# CPU.net
KiCad netlist of a schematic drawn in Altium Designer
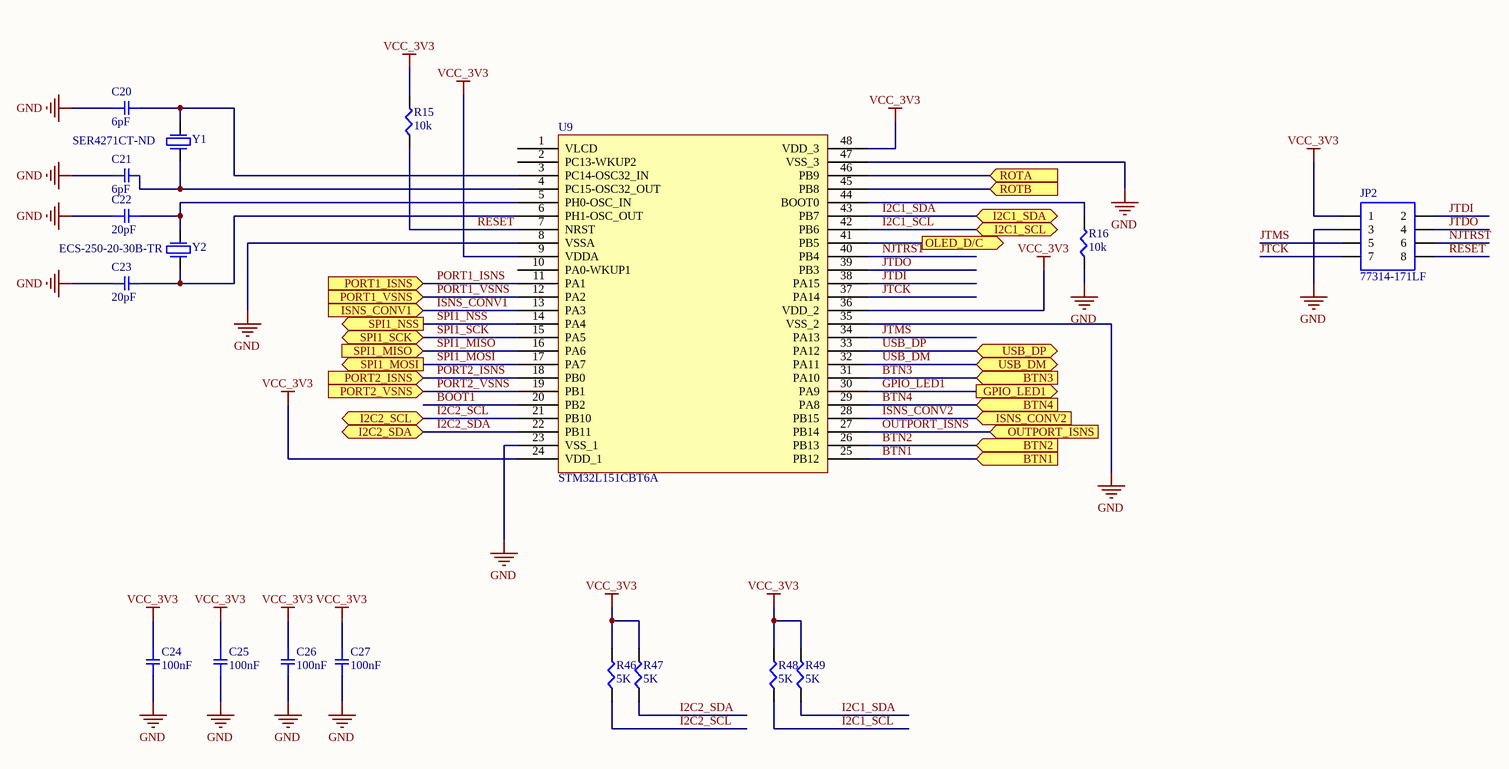
[diagram p0: CPU.SchDoc]

(export (version "E")
  (design (tool "Eeschema 10.0.6"))
  (components
    (comp (ref "C20")
      (value "6pF")
      (footprint "SMD-0805C")
      (description "CAP CER 0.1UF 50V X7R 0805")
      (fields
        (field (name "DIGI-KEY PART NUMBER") "490-6064-1-ND")
        (field (name "PART NUMBER") "GCM21BR71H104KA37L")
      )
      (libsource (lib "capacitor_murata_0805") (part "GCM21BR71H104KA37L"))
    )
    (comp (ref "C21")
      (value "6pF")
      (footprint "SMD-0805C")
      (description "CAP CER 0.1UF 50V X7R 0805")
      (fields
        (field (name "DIGI-KEY PART NUMBER") "490-6064-1-ND")
        (field (name "PART NUMBER") "GCM21BR71H104KA37L")
      )
      (libsource (lib "capacitor_murata_0805") (part "GCM21BR71H104KA37L"))
    )
    (comp (ref "C22")
      (value "20pF")
      (footprint "SMD-0805C")
      (description "CAP CER 0.1UF 50V X7R 0805")
      (fields
        (field (name "DIGI-KEY PART NUMBER") "490-6064-1-ND")
        (field (name "PART NUMBER") "GCM21BR71H104KA37L")
      )
      (libsource (lib "capacitor_murata_0805") (part "GCM21BR71H104KA37L"))
    )
    (comp (ref "C23")
      (value "20pF")
      (footprint "SMD-0805C")
      (description "CAP CER 0.1UF 50V X7R 0805")
      (fields
        (field (name "DIGI-KEY PART NUMBER") "490-6064-1-ND")
        (field (name "PART NUMBER") "GCM21BR71H104KA37L")
      )
      (libsource (lib "capacitor_murata_0805") (part "GCM21BR71H104KA37L"))
    )
    (comp (ref "C24")
      (value "100nF")
      (footprint "SMD-0805C")
      (description "CAP CER 0.1UF 50V X7R 0805")
      (fields
        (field (name "DIGI-KEY PART NUMBER") "490-6064-1-ND")
        (field (name "PART NUMBER") "GCM21BR71H104KA37L")
      )
      (libsource (lib "capacitor_murata_0805") (part "GCM21BR71H104KA37L"))
    )
    (comp (ref "C25")
      (value "100nF")
      (footprint "SMD-0805C")
      (description "CAP CER 0.1UF 50V X7R 0805")
      (fields
        (field (name "DIGI-KEY PART NUMBER") "490-6064-1-ND")
        (field (name "PART NUMBER") "GCM21BR71H104KA37L")
      )
      (libsource (lib "capacitor_murata_0805") (part "GCM21BR71H104KA37L"))
    )
    (comp (ref "C26")
      (value "100nF")
      (footprint "SMD-0805C")
      (description "CAP CER 0.1UF 50V X7R 0805")
      (fields
        (field (name "DIGI-KEY PART NUMBER") "490-6064-1-ND")
        (field (name "PART NUMBER") "GCM21BR71H104KA37L")
      )
      (libsource (lib "capacitor_murata_0805") (part "GCM21BR71H104KA37L"))
    )
    (comp (ref "C27")
      (value "100nF")
      (footprint "SMD-0805C")
      (description "CAP CER 0.1UF 50V X7R 0805")
      (fields
        (field (name "DIGI-KEY PART NUMBER") "490-6064-1-ND")
        (field (name "PART NUMBER") "GCM21BR71H104KA37L")
      )
      (libsource (lib "capacitor_murata_0805") (part "GCM21BR71H104KA37L"))
    )
    (comp (ref "JP2")
      (value "77314-171LF")
      (footprint "2x4 Pin Header")
      (description "CONN HEADER VERT 8POS 2.54MM")
      (libsource (lib "Personal_Library") (part "CONN HEADER VERT 2x4"))
    )
    (comp (ref "R15")
      (value "10k")
      (footprint "SMD-0603-RES")
      (description "RES SMD 1.6 OHM 1% 1/4W 0603")
      (fields (field (name "PART NUMBER") "ERJ-3BQF1R6V") (field (name "DIGI-KEY PART NUMBER") "P17375CT-ND"))
      (libsource (lib "Panasonic_ERJ_0603") (part "ERJ-3BQF1R6V"))
    )
    (comp (ref "R16")
      (value "10k")
      (footprint "SMD-0603-RES")
      (description "RES SMD 1.6 OHM 1% 1/4W 0603")
      (fields (field (name "PART NUMBER") "ERJ-3BQF1R6V") (field (name "DIGI-KEY PART NUMBER") "P17375CT-ND"))
      (libsource (lib "Panasonic_ERJ_0603") (part "ERJ-3BQF1R6V"))
    )
    (comp (ref "R46")
      (value "5K")
      (footprint "SMD-0603-RES")
      (description "RES SMD 1.5 OHM 1% 1/4W 0603")
      (fields (field (name "PART NUMBER") "ERJ-3BQF1R5V") (field (name "DIGI-KEY PART NUMBER") "P15988CT-ND"))
      (libsource (lib "Panasonic_ERJ_0603") (part "ERJ-3BQF1R5V"))
    )
    (comp (ref "R47")
      (value "5K")
      (footprint "SMD-0603-RES")
      (description "RES SMD 1.5 OHM 1% 1/4W 0603")
      (fields (field (name "PART NUMBER") "ERJ-3BQF1R5V") (field (name "DIGI-KEY PART NUMBER") "P15988CT-ND"))
      (libsource (lib "Panasonic_ERJ_0603") (part "ERJ-3BQF1R5V"))
    )
    (comp (ref "R48")
      (value "5K")
      (footprint "SMD-0603-RES")
      (description "RES SMD 1.5 OHM 1% 1/4W 0603")
      (fields (field (name "PART NUMBER") "ERJ-3BQF1R5V") (field (name "DIGI-KEY PART NUMBER") "P15988CT-ND"))
      (libsource (lib "Panasonic_ERJ_0603") (part "ERJ-3BQF1R5V"))
    )
    (comp (ref "R49")
      (value "5K")
      (footprint "SMD-0603-RES")
      (description "RES SMD 1.5 OHM 1% 1/4W 0603")
      (fields (field (name "PART NUMBER") "ERJ-3BQF1R5V") (field (name "DIGI-KEY PART NUMBER") "P15988CT-ND"))
      (libsource (lib "Panasonic_ERJ_0603") (part "ERJ-3BQF1R5V"))
    )
    (comp (ref "U9")
      (value "STM32L151CBT6A")
      (footprint "LQFP_151CBT6A_STM")
      (description "No Description Available")
      (fields (field (name "COPYRIGHT") "Copyright (C) 2018 Accelerated Designs. All rights reserved"))
      (libsource (lib "UniversalConverter_Parts") (part "IC STM32L151CBT6A_1"))
    )
    (comp (ref "Y1")
      (value "SER4271CT-ND")
      (footprint "ABS07-120")
      (description "32.768kHz ±20ppm Crystal 6pF 55 kOhms 2-SMD, No Lead")
      (libsource (lib "Personal_Library") (part "CRYSTAL 32.7680KHZ"))
    )
    (comp (ref "Y2")
      (value "ECS-250-20-30B-TR")
      (footprint "4-SMD XTAL")
      (description "CRYSTAL 20MHZ 18PF SMD")
      (libsource (lib "Personal_Library") (part "CRYSTAL 20MHZ"))
    )
  )
  (nets
    (net (code "1") (name "/BOOT1") (class "Default")
      (node (ref "U9") (pin "20") (pinfunction "PB2_20") (pintype "passive"))
    )
    (net (code "2") (name "/BTN1") (class "Default")
      (node (ref "U9") (pin "25") (pinfunction "PB12_25") (pintype "passive"))
    )
    (net (code "3") (name "/BTN2") (class "Default")
      (node (ref "U9") (pin "26") (pinfunction "PB13_26") (pintype "passive"))
    )
    (net (code "4") (name "/BTN3") (class "Default")
      (node (ref "U9") (pin "31") (pinfunction "PA10_31") (pintype "passive"))
    )
    (net (code "5") (name "/BTN4") (class "Default")
      (node (ref "U9") (pin "29") (pinfunction "PA8_29") (pintype "passive"))
    )
    (net (code "6") (name "/GPIO_LED1") (class "Default")
      (node (ref "U9") (pin "30") (pinfunction "PA9_30") (pintype "passive"))
    )
    (net (code "7") (name "/I2C1_SCL") (class "Default")
      (node (ref "R48") (pin "1") (pinfunction "1_1") (pintype "passive"))
      (node (ref "U9") (pin "42") (pinfunction "PB6_42") (pintype "passive"))
    )
    (net (code "8") (name "/I2C1_SDA") (class "Default")
      (node (ref "R49") (pin "1") (pinfunction "1_1") (pintype "passive"))
      (node (ref "U9") (pin "43") (pinfunction "PB7_43") (pintype "passive"))
    )
    (net (code "9") (name "/I2C2_SCL") (class "Default")
      (node (ref "R46") (pin "1") (pinfunction "1_1") (pintype "passive"))
      (node (ref "U9") (pin "21") (pinfunction "PB10_21") (pintype "passive"))
    )
    (net (code "10") (name "/I2C2_SDA") (class "Default")
      (node (ref "R47") (pin "1") (pinfunction "1_1") (pintype "passive"))
      (node (ref "U9") (pin "22") (pinfunction "PB11_22") (pintype "passive"))
    )
    (net (code "11") (name "/ISNS_CONV1") (class "Default")
      (node (ref "U9") (pin "13") (pinfunction "PA3_13") (pintype "passive"))
    )
    (net (code "12") (name "/ISNS_CONV2") (class "Default")
      (node (ref "U9") (pin "28") (pinfunction "PB15_28") (pintype "passive"))
    )
    (net (code "13") (name "/JTCK") (class "Default")
      (node (ref "JP2") (pin "7") (pinfunction "7_7") (pintype "passive"))
      (node (ref "U9") (pin "37") (pinfunction "PA14_37") (pintype "passive"))
    )
    (net (code "14") (name "/JTDI") (class "Default")
      (node (ref "JP2") (pin "2") (pinfunction "2_2") (pintype "passive"))
      (node (ref "U9") (pin "38") (pinfunction "PA15_38") (pintype "passive"))
    )
    (net (code "15") (name "/JTDO") (class "Default")
      (node (ref "JP2") (pin "4") (pinfunction "4_4") (pintype "passive"))
      (node (ref "U9") (pin "39") (pinfunction "PB3_39") (pintype "passive"))
    )
    (net (code "16") (name "/JTMS") (class "Default")
      (node (ref "JP2") (pin "5") (pinfunction "5_5") (pintype "passive"))
      (node (ref "U9") (pin "34") (pinfunction "PA13_34") (pintype "passive"))
    )
    (net (code "17") (name "/NJTRST") (class "Default")
      (node (ref "JP2") (pin "6") (pinfunction "6_6") (pintype "passive"))
      (node (ref "U9") (pin "40") (pinfunction "PB4_40") (pintype "passive"))
    )
    (net (code "18") (name "/OLED_D{slash}C") (class "Default")
      (node (ref "U9") (pin "41") (pinfunction "PB5_41") (pintype "passive"))
    )
    (net (code "19") (name "/OUTPORT_ISNS") (class "Default")
      (node (ref "U9") (pin "27") (pinfunction "PB14_27") (pintype "passive"))
    )
    (net (code "20") (name "/PORT1_ISNS") (class "Default")
      (node (ref "U9") (pin "11") (pinfunction "PA1_11") (pintype "passive"))
    )
    (net (code "21") (name "/PORT1_VSNS") (class "Default")
      (node (ref "U9") (pin "12") (pinfunction "PA2_12") (pintype "passive"))
    )
    (net (code "22") (name "/PORT2_ISNS") (class "Default")
      (node (ref "U9") (pin "18") (pinfunction "PB0_18") (pintype "passive"))
    )
    (net (code "23") (name "/PORT2_VSNS") (class "Default")
      (node (ref "U9") (pin "19") (pinfunction "PB1_19") (pintype "passive"))
    )
    (net (code "24") (name "/RESET") (class "Default")
      (node (ref "JP2") (pin "8") (pinfunction "8_8") (pintype "passive"))
      (node (ref "R15") (pin "1") (pinfunction "1_1") (pintype "passive"))
      (node (ref "U9") (pin "7") (pinfunction "NRST_7") (pintype "passive"))
    )
    (net (code "25") (name "/ROTA") (class "Default")
      (node (ref "U9") (pin "46") (pinfunction "PB9_46") (pintype "passive"))
    )
    (net (code "26") (name "/ROTB") (class "Default")
      (node (ref "U9") (pin "45") (pinfunction "PB8_45") (pintype "passive"))
    )
    (net (code "27") (name "/SPI1_MISO") (class "Default")
      (node (ref "U9") (pin "16") (pinfunction "PA6_16") (pintype "passive"))
    )
    (net (code "28") (name "/SPI1_MOSI") (class "Default")
      (node (ref "U9") (pin "17") (pinfunction "PA7_17") (pintype "passive"))
    )
    (net (code "29") (name "/SPI1_NSS") (class "Default")
      (node (ref "U9") (pin "14") (pinfunction "PA4_14") (pintype "passive"))
    )
    (net (code "30") (name "/SPI1_SCK") (class "Default")
      (node (ref "U9") (pin "15") (pinfunction "PA5_15") (pintype "passive"))
    )
    (net (code "31") (name "/USB_DM") (class "Default")
      (node (ref "U9") (pin "32") (pinfunction "PA11_32") (pintype "passive"))
    )
    (net (code "32") (name "/USB_DP") (class "Default")
      (node (ref "U9") (pin "33") (pinfunction "PA12_33") (pintype "passive"))
    )
    (net (code "33") (name "GND") (class "Default")
      (node (ref "C20") (pin "1") (pinfunction "1_1") (pintype "passive"))
      (node (ref "C21") (pin "1") (pinfunction "1_1") (pintype "passive"))
      (node (ref "C22") (pin "1") (pinfunction "1_1") (pintype "passive"))
      (node (ref "C23") (pin "1") (pinfunction "1_1") (pintype "passive"))
      (node (ref "C24") (pin "2") (pinfunction "2_2") (pintype "passive"))
      (node (ref "C25") (pin "2") (pinfunction "2_2") (pintype "passive"))
      (node (ref "C26") (pin "2") (pinfunction "2_2") (pintype "passive"))
      (node (ref "C27") (pin "2") (pinfunction "2_2") (pintype "passive"))
      (node (ref "JP2") (pin "3") (pinfunction "3_3") (pintype "passive"))
      (node (ref "R16") (pin "1") (pinfunction "1_1") (pintype "passive"))
      (node (ref "U9") (pin "23") (pinfunction "VSS_1_23") (pintype "passive"))
      (node (ref "U9") (pin "35") (pinfunction "VSS_2_35") (pintype "passive"))
      (node (ref "U9") (pin "47") (pinfunction "VSS_3_47") (pintype "passive"))
      (node (ref "U9") (pin "8") (pinfunction "VSSA_8") (pintype "passive"))
    )
    (net (code "34") (name "Net-(U9-BOOT0)") (class "Default")
      (node (ref "R16") (pin "2") (pinfunction "2_2") (pintype "passive"))
      (node (ref "U9") (pin "44") (pinfunction "BOOT0_44") (pintype "passive"))
    )
    (net (code "35") (name "Net-(U9-PC14-OSC32_IN)") (class "Default")
      (node (ref "C20") (pin "2") (pinfunction "2_2") (pintype "passive"))
      (node (ref "U9") (pin "3") (pinfunction "PC14-OSC32_IN_3") (pintype "passive"))
      (node (ref "Y1") (pin "1") (pinfunction "1_1") (pintype "passive"))
    )
    (net (code "36") (name "Net-(U9-PC15-OSC32_OUT)") (class "Default")
      (node (ref "C21") (pin "2") (pinfunction "2_2") (pintype "passive"))
      (node (ref "U9") (pin "4") (pinfunction "PC15-OSC32_OUT_4") (pintype "passive"))
      (node (ref "Y1") (pin "2") (pinfunction "2_2") (pintype "passive"))
    )
    (net (code "37") (name "Net-(U9-PH0-OSC_IN)") (class "Default")
      (node (ref "C22") (pin "2") (pinfunction "2_2") (pintype "passive"))
      (node (ref "U9") (pin "5") (pinfunction "PH0-OSC_IN_5") (pintype "passive"))
      (node (ref "Y2") (pin "1") (pinfunction "1_1") (pintype "passive"))
    )
    (net (code "38") (name "Net-(U9-PH1-OSC_OUT)") (class "Default")
      (node (ref "C23") (pin "2") (pinfunction "2_2") (pintype "passive"))
      (node (ref "U9") (pin "6") (pinfunction "PH1-OSC_OUT_6") (pintype "passive"))
      (node (ref "Y2") (pin "3") (pinfunction "3_3") (pintype "passive"))
    )
    (net (code "39") (name "VCC_3V3") (class "Default")
      (node (ref "C24") (pin "1") (pinfunction "1_1") (pintype "passive"))
      (node (ref "C25") (pin "1") (pinfunction "1_1") (pintype "passive"))
      (node (ref "C26") (pin "1") (pinfunction "1_1") (pintype "passive"))
      (node (ref "C27") (pin "1") (pinfunction "1_1") (pintype "passive"))
      (node (ref "JP2") (pin "1") (pinfunction "1_1") (pintype "passive"))
      (node (ref "R15") (pin "2") (pinfunction "2_2") (pintype "passive"))
      (node (ref "R46") (pin "2") (pinfunction "2_2") (pintype "passive"))
      (node (ref "R47") (pin "2") (pinfunction "2_2") (pintype "passive"))
      (node (ref "R48") (pin "2") (pinfunction "2_2") (pintype "passive"))
      (node (ref "R49") (pin "2") (pinfunction "2_2") (pintype "passive"))
      (node (ref "U9") (pin "24") (pinfunction "VDD_1_24") (pintype "passive"))
      (node (ref "U9") (pin "36") (pinfunction "VDD_2_36") (pintype "passive"))
      (node (ref "U9") (pin "48") (pinfunction "VDD_3_48") (pintype "passive"))
      (node (ref "U9") (pin "9") (pinfunction "VDDA_9") (pintype "passive"))
    )
    (net (code "40") (name "unconnected-(U9-PA0-WKUP1-Pad10)") (class "Default")
      (node (ref "U9") (pin "10") (pinfunction "PA0-WKUP1_10") (pintype "passive"))
    )
    (net (code "41") (name "unconnected-(U9-PC13-WKUP2-Pad2)") (class "Default")
      (node (ref "U9") (pin "2") (pinfunction "PC13-WKUP2_2") (pintype "passive"))
    )
    (net (code "42") (name "unconnected-(U9-VLCD-Pad1)") (class "Default")
      (node (ref "U9") (pin "1") (pinfunction "VLCD_1") (pintype "passive"))
    )
  )
)
